# GroundStation.net
KiCad netlist of a schematic drawn in EAGLE
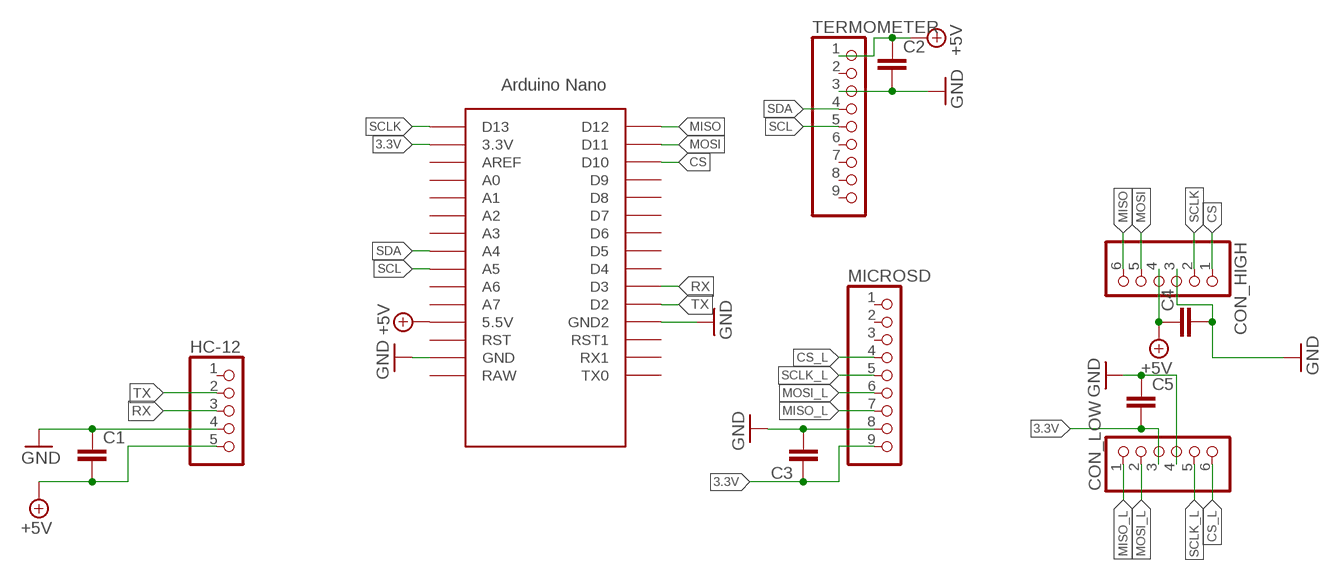
[diagram p0: schematic, sheet 1]

(export (version "E")
  (design (tool "Eeschema 10.0.6"))
  (components
    (comp (ref "C1")
      (value "C-EU050-025X075")
      (footprint "eagle-import:C050-025X075")
      (libsource (lib "eagle-import") (part "C-EU050-025X075"))
    )
    (comp (ref "C2")
      (value "C-EU050-025X075")
      (footprint "eagle-import:C050-025X075")
      (libsource (lib "eagle-import") (part "C-EU050-025X075"))
    )
    (comp (ref "C3")
      (value "C-EU050-025X075")
      (footprint "eagle-import:C050-025X075")
      (libsource (lib "eagle-import") (part "C-EU050-025X075"))
    )
    (comp (ref "C4")
      (value "C-EU050-025X075")
      (footprint "eagle-import:C050-025X075")
      (libsource (lib "eagle-import") (part "C-EU050-025X075"))
    )
    (comp (ref "C5")
      (value "C-EU050-025X075")
      (footprint "eagle-import:C050-025X075")
      (libsource (lib "eagle-import") (part "C-EU050-025X075"))
    )
    (comp (ref "CON_HIGH")
      (value "PINHD-1X6")
      (footprint "eagle-import:1X06")
      (libsource (lib "eagle-import") (part "PINHD-1X6"))
    )
    (comp (ref "CON_LOW")
      (value "PINHD-1X6")
      (footprint "eagle-import:1X06")
      (libsource (lib "eagle-import") (part "PINHD-1X6"))
    )
    (comp (ref "HC-12")
      (value "PINHD-1X5")
      (footprint "eagle-import:1X05")
      (libsource (lib "eagle-import") (part "PINHD-1X5"))
    )
    (comp (ref "MICROSD")
      (value "PINHD-1X9")
      (footprint "eagle-import:1X09")
      (libsource (lib "eagle-import") (part "PINHD-1X9"))
    )
    (comp (ref "TERMOMETER")
      (value "PINHD-1X9")
      (footprint "eagle-import:1X09")
      (libsource (lib "eagle-import") (part "PINHD-1X9"))
    )
    (comp (ref "U$1")
      (value "NANO")
      (footprint "eagle-import:NANO")
      (libsource (lib "eagle-import") (part "NANO"))
    )
  )
  (nets
    (net (code "1") (name "+5V") (class "Default")
      (node (ref "C1") (pin "2") (pinfunction "2_2") (pintype "passive"))
      (node (ref "C2") (pin "1") (pinfunction "1_1") (pintype "passive"))
      (node (ref "C4") (pin "1") (pinfunction "1_1") (pintype "passive"))
      (node (ref "CON_HIGH") (pin "4") (pinfunction "4_4") (pintype "passive"))
      (node (ref "HC-12") (pin "5") (pinfunction "5_5") (pintype "passive"))
      (node (ref "TERMOMETER") (pin "1") (pinfunction "1_1") (pintype "passive"))
      (node (ref "U$1") (pin "5V") (pinfunction "5.5V_5V") (pintype "bidirectional"))
    )
    (net (code "2") (name "3.3V") (class "Default")
      (node (ref "C3") (pin "1") (pinfunction "1_1") (pintype "passive"))
      (node (ref "C5") (pin "2") (pinfunction "2_2") (pintype "passive"))
      (node (ref "CON_LOW") (pin "3") (pinfunction "3_3") (pintype "passive"))
      (node (ref "MICROSD") (pin "9") (pinfunction "9_9") (pintype "passive"))
      (node (ref "U$1") (pin "3.3V") (pinfunction "3.3V_3.3V") (pintype "bidirectional"))
    )
    (net (code "3") (name "CS") (class "Default")
      (node (ref "CON_HIGH") (pin "1") (pinfunction "1_1") (pintype "passive"))
      (node (ref "U$1") (pin "D10") (pinfunction "D10_D10") (pintype "bidirectional"))
    )
    (net (code "4") (name "CS_L") (class "Default")
      (node (ref "CON_LOW") (pin "6") (pinfunction "6_6") (pintype "passive"))
      (node (ref "MICROSD") (pin "4") (pinfunction "4_4") (pintype "passive"))
    )
    (net (code "5") (name "GND") (class "Default")
      (node (ref "C1") (pin "1") (pinfunction "1_1") (pintype "passive"))
      (node (ref "C2") (pin "2") (pinfunction "2_2") (pintype "passive"))
      (node (ref "C3") (pin "2") (pinfunction "2_2") (pintype "passive"))
      (node (ref "C4") (pin "2") (pinfunction "2_2") (pintype "passive"))
      (node (ref "C5") (pin "1") (pinfunction "1_1") (pintype "passive"))
      (node (ref "CON_HIGH") (pin "3") (pinfunction "3_3") (pintype "passive"))
      (node (ref "CON_LOW") (pin "4") (pinfunction "4_4") (pintype "passive"))
      (node (ref "HC-12") (pin "4") (pinfunction "4_4") (pintype "passive"))
      (node (ref "MICROSD") (pin "8") (pinfunction "8_8") (pintype "passive"))
      (node (ref "TERMOMETER") (pin "3") (pinfunction "3_3") (pintype "passive"))
      (node (ref "U$1") (pin "GND") (pinfunction "GND_GND") (pintype "bidirectional"))
      (node (ref "U$1") (pin "GND1") (pinfunction "GND2_GND1") (pintype "bidirectional"))
    )
    (net (code "6") (name "MISO") (class "Default")
      (node (ref "CON_HIGH") (pin "6") (pinfunction "6_6") (pintype "passive"))
      (node (ref "U$1") (pin "D12") (pinfunction "D12_D12") (pintype "bidirectional"))
    )
    (net (code "7") (name "MISO_L") (class "Default")
      (node (ref "CON_LOW") (pin "1") (pinfunction "1_1") (pintype "passive"))
      (node (ref "MICROSD") (pin "7") (pinfunction "7_7") (pintype "passive"))
    )
    (net (code "8") (name "MOSI") (class "Default")
      (node (ref "CON_HIGH") (pin "5") (pinfunction "5_5") (pintype "passive"))
      (node (ref "U$1") (pin "D11") (pinfunction "D11_D11") (pintype "bidirectional"))
    )
    (net (code "9") (name "MOSI_L") (class "Default")
      (node (ref "CON_LOW") (pin "2") (pinfunction "2_2") (pintype "passive"))
      (node (ref "MICROSD") (pin "6") (pinfunction "6_6") (pintype "passive"))
    )
    (net (code "10") (name "RX") (class "Default")
      (node (ref "HC-12") (pin "3") (pinfunction "3_3") (pintype "passive"))
      (node (ref "U$1") (pin "D3") (pinfunction "D3_D3") (pintype "bidirectional"))
    )
    (net (code "11") (name "SCL") (class "Default")
      (node (ref "TERMOMETER") (pin "5") (pinfunction "5_5") (pintype "passive"))
      (node (ref "U$1") (pin "A5") (pinfunction "A5_A5") (pintype "bidirectional"))
    )
    (net (code "12") (name "SCLK") (class "Default")
      (node (ref "CON_HIGH") (pin "2") (pinfunction "2_2") (pintype "passive"))
      (node (ref "U$1") (pin "D13") (pinfunction "D13_D13") (pintype "bidirectional"))
    )
    (net (code "13") (name "SCLK_L") (class "Default")
      (node (ref "CON_LOW") (pin "5") (pinfunction "5_5") (pintype "passive"))
      (node (ref "MICROSD") (pin "5") (pinfunction "5_5") (pintype "passive"))
    )
    (net (code "14") (name "SDA") (class "Default")
      (node (ref "TERMOMETER") (pin "4") (pinfunction "4_4") (pintype "passive"))
      (node (ref "U$1") (pin "A4") (pinfunction "A4_A4") (pintype "bidirectional"))
    )
    (net (code "15") (name "TX") (class "Default")
      (node (ref "HC-12") (pin "2") (pinfunction "2_2") (pintype "passive"))
      (node (ref "U$1") (pin "D2") (pinfunction "D2_D2") (pintype "bidirectional"))
    )
    (net (code "16") (name "unconnected-(HC-12-Pad1)") (class "Default")
      (node (ref "HC-12") (pin "1") (pinfunction "1_1") (pintype "passive"))
    )
    (net (code "17") (name "unconnected-(MICROSD-Pad1)") (class "Default")
      (node (ref "MICROSD") (pin "1") (pinfunction "1_1") (pintype "passive"))
    )
    (net (code "18") (name "unconnected-(MICROSD-Pad2)") (class "Default")
      (node (ref "MICROSD") (pin "2") (pinfunction "2_2") (pintype "passive"))
    )
    (net (code "19") (name "unconnected-(MICROSD-Pad3)") (class "Default")
      (node (ref "MICROSD") (pin "3") (pinfunction "3_3") (pintype "passive"))
    )
    (net (code "20") (name "unconnected-(TERMOMETER-Pad2)") (class "Default")
      (node (ref "TERMOMETER") (pin "2") (pinfunction "2_2") (pintype "passive"))
    )
    (net (code "21") (name "unconnected-(TERMOMETER-Pad6)") (class "Default")
      (node (ref "TERMOMETER") (pin "6") (pinfunction "6_6") (pintype "passive"))
    )
    (net (code "22") (name "unconnected-(TERMOMETER-Pad7)") (class "Default")
      (node (ref "TERMOMETER") (pin "7") (pinfunction "7_7") (pintype "passive"))
    )
    (net (code "23") (name "unconnected-(TERMOMETER-Pad8)") (class "Default")
      (node (ref "TERMOMETER") (pin "8") (pinfunction "8_8") (pintype "passive"))
    )
    (net (code "24") (name "unconnected-(TERMOMETER-Pad9)") (class "Default")
      (node (ref "TERMOMETER") (pin "9") (pinfunction "9_9") (pintype "passive"))
    )
    (net (code "25") (name "unconnected-(U$1-PadA0)") (class "Default")
      (node (ref "U$1") (pin "A0") (pinfunction "A0_A0") (pintype "bidirectional"))
    )
    (net (code "26") (name "unconnected-(U$1-PadA1)") (class "Default")
      (node (ref "U$1") (pin "A1") (pinfunction "A1_A1") (pintype "bidirectional"))
    )
    (net (code "27") (name "unconnected-(U$1-PadA2)") (class "Default")
      (node (ref "U$1") (pin "A2") (pinfunction "A2_A2") (pintype "bidirectional"))
    )
    (net (code "28") (name "unconnected-(U$1-PadA3)") (class "Default")
      (node (ref "U$1") (pin "A3") (pinfunction "A3_A3") (pintype "bidirectional"))
    )
    (net (code "29") (name "unconnected-(U$1-PadA6)") (class "Default")
      (node (ref "U$1") (pin "A6") (pinfunction "A6_A6") (pintype "bidirectional"))
    )
    (net (code "30") (name "unconnected-(U$1-PadA7)") (class "Default")
      (node (ref "U$1") (pin "A7") (pinfunction "A7_A7") (pintype "bidirectional"))
    )
    (net (code "31") (name "unconnected-(U$1-PadAREF)") (class "Default")
      (node (ref "U$1") (pin "AREF") (pinfunction "AREF_AREF") (pintype "bidirectional"))
    )
    (net (code "32") (name "unconnected-(U$1-PadD4)") (class "Default")
      (node (ref "U$1") (pin "D4") (pinfunction "D4_D4") (pintype "bidirectional"))
    )
    (net (code "33") (name "unconnected-(U$1-PadD5)") (class "Default")
      (node (ref "U$1") (pin "D5") (pinfunction "D5_D5") (pintype "bidirectional"))
    )
    (net (code "34") (name "unconnected-(U$1-PadD6)") (class "Default")
      (node (ref "U$1") (pin "D6") (pinfunction "D6_D6") (pintype "bidirectional"))
    )
    (net (code "35") (name "unconnected-(U$1-PadD7)") (class "Default")
      (node (ref "U$1") (pin "D7") (pinfunction "D7_D7") (pintype "bidirectional"))
    )
    (net (code "36") (name "unconnected-(U$1-PadD8)") (class "Default")
      (node (ref "U$1") (pin "D8") (pinfunction "D8_D8") (pintype "bidirectional"))
    )
    (net (code "37") (name "unconnected-(U$1-PadD9)") (class "Default")
      (node (ref "U$1") (pin "D9") (pinfunction "D9_D9") (pintype "bidirectional"))
    )
    (net (code "38") (name "unconnected-(U$1-PadICSP1)") (class "Default")
      (node (ref "U$1") (pin "ICSP1") (pinfunction "ICSP1_ICSP1") (pintype "bidirectional"))
    )
    (net (code "39") (name "unconnected-(U$1-PadICSP2)") (class "Default")
      (node (ref "U$1") (pin "ICSP2") (pinfunction "ICSP2_ICSP2") (pintype "bidirectional"))
    )
    (net (code "40") (name "unconnected-(U$1-PadICSP3)") (class "Default")
      (node (ref "U$1") (pin "ICSP3") (pinfunction "ICSP3_ICSP3") (pintype "bidirectional"))
    )
    (net (code "41") (name "unconnected-(U$1-PadICSP4)") (class "Default")
      (node (ref "U$1") (pin "ICSP4") (pinfunction "ICSP4_ICSP4") (pintype "bidirectional"))
    )
    (net (code "42") (name "unconnected-(U$1-PadICSP5)") (class "Default")
      (node (ref "U$1") (pin "ICSP5") (pinfunction "ICSP5_ICSP5") (pintype "bidirectional"))
    )
    (net (code "43") (name "unconnected-(U$1-PadICSP6)") (class "Default")
      (node (ref "U$1") (pin "ICSP6") (pinfunction "ICSP6_ICSP6") (pintype "bidirectional"))
    )
    (net (code "44") (name "unconnected-(U$1-PadRAW)") (class "Default")
      (node (ref "U$1") (pin "RAW") (pinfunction "RAW_RAW") (pintype "bidirectional"))
    )
    (net (code "45") (name "unconnected-(U$1-PadRST)") (class "Default")
      (node (ref "U$1") (pin "RST") (pinfunction "RST_RST") (pintype "bidirectional"))
    )
    (net (code "46") (name "unconnected-(U$1-PadRST1)") (class "Default")
      (node (ref "U$1") (pin "RST1") (pinfunction "RST1_RST1") (pintype "bidirectional"))
    )
    (net (code "47") (name "unconnected-(U$1-PadRX1)") (class "Default")
      (node (ref "U$1") (pin "RX1") (pinfunction "RX1_RX1") (pintype "bidirectional"))
    )
    (net (code "48") (name "unconnected-(U$1-PadTX0)") (class "Default")
      (node (ref "U$1") (pin "TX0") (pinfunction "TX0_TX0") (pintype "bidirectional"))
    )
  )
)
